# lps_regulator_rev_12.net
KiCad netlist of a schematic drawn in Altium Designer
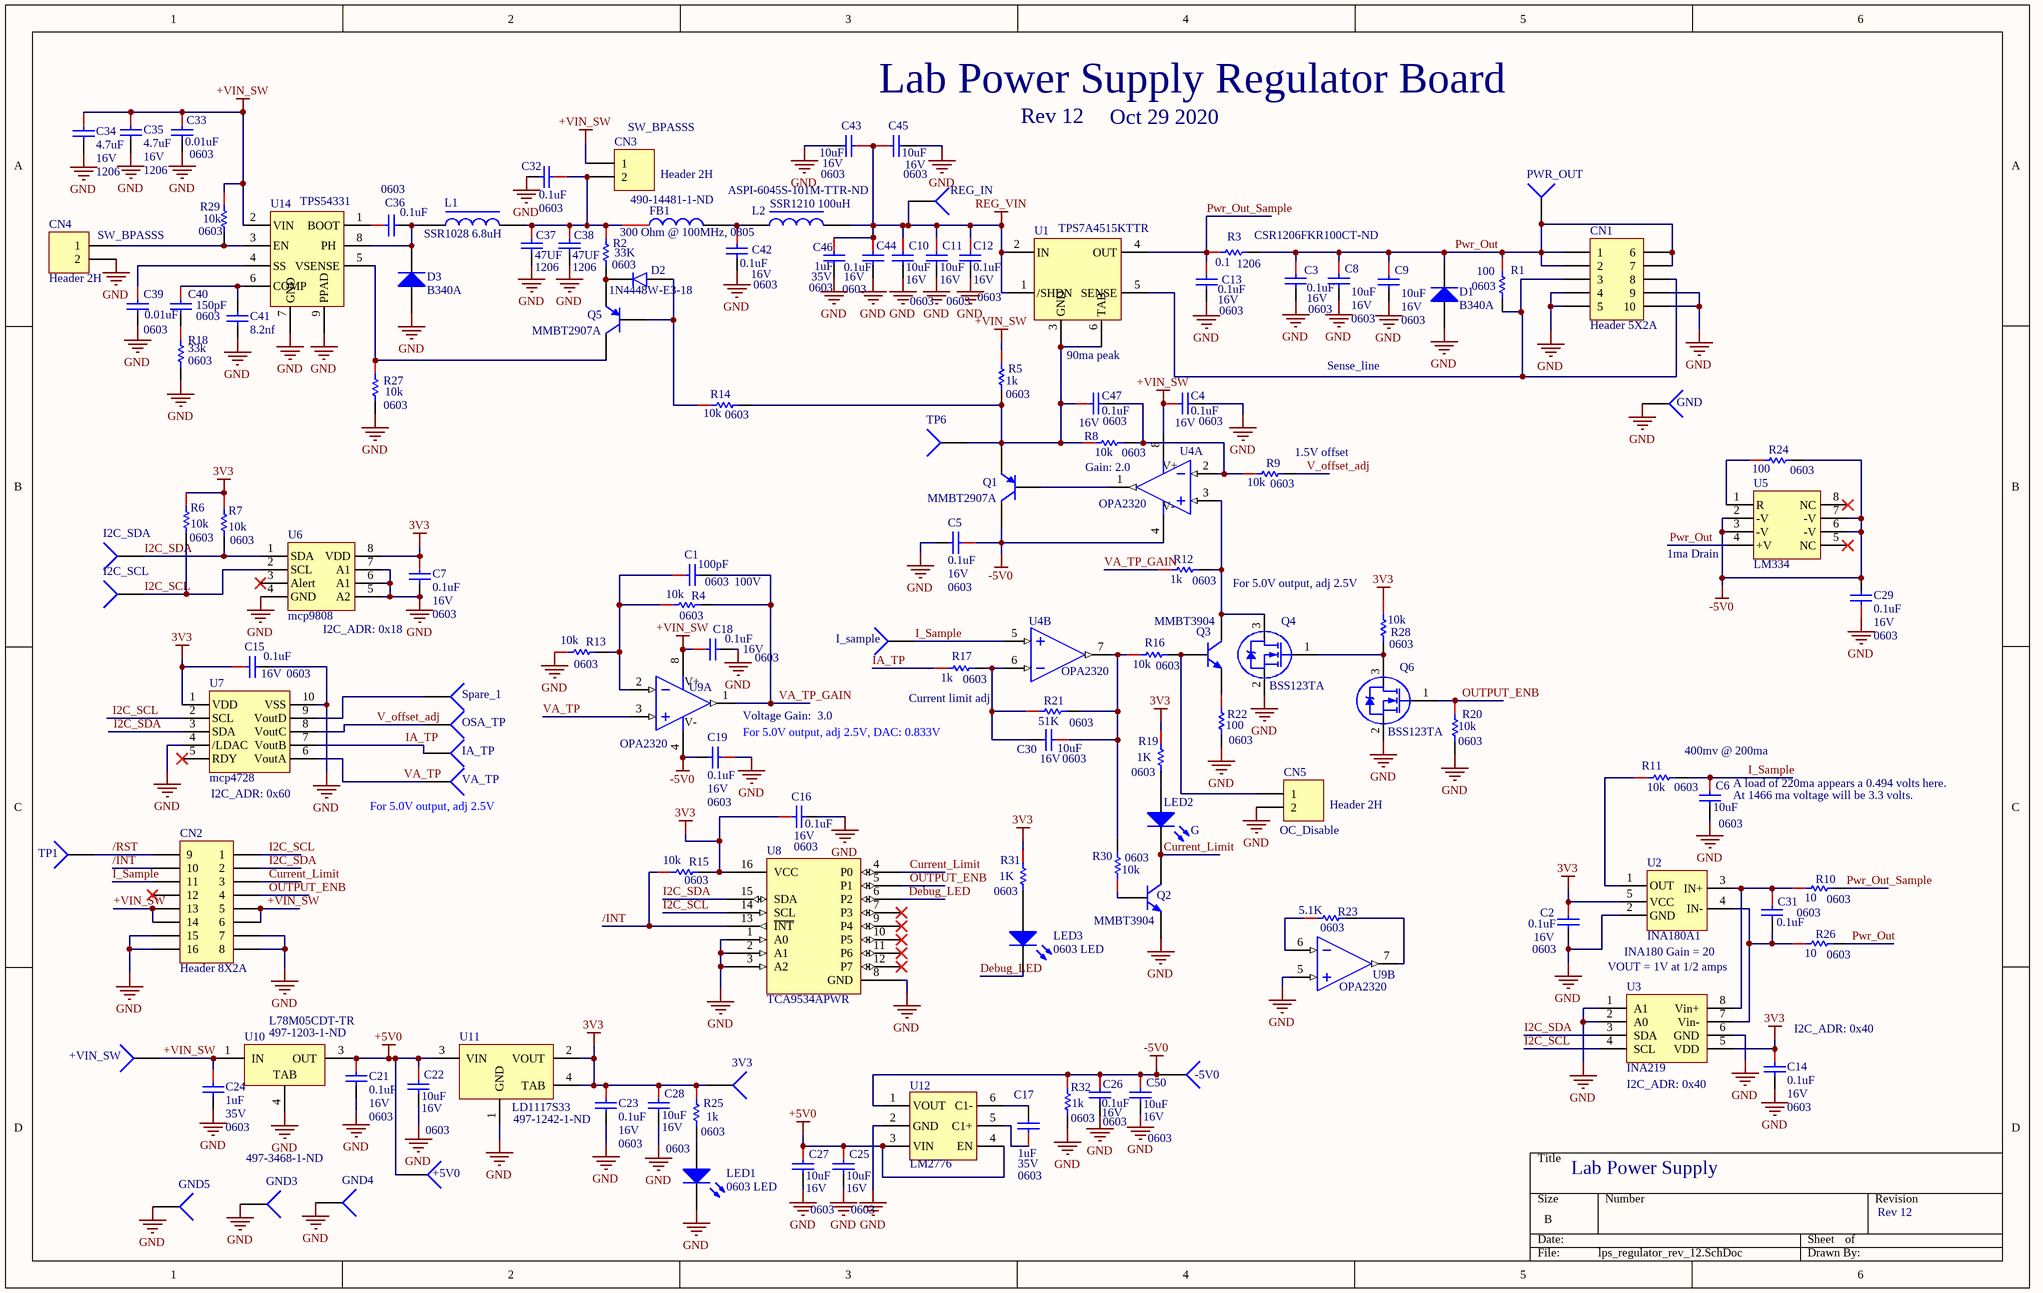
[diagram p0: lps_regulator_rev_12.SchDoc]

(export (version "E")
  (design (tool "Eeschema 10.0.6"))
  (components
    (comp (ref "+5V0")
      (value "TestPoint_BLK")
      (footprint "TestPoint-TH 42 mil")
      (description "Test Point - Black")
      (fields
        (field (name "MANUFACTURER PART NUMBER") "5001")
        (field (name "MANUFACTURER") "Keystone Electronics")
      )
      (libsource (lib "OLogic Nexus Vault") (part "TestPoint_BLK"))
    )
    (comp (ref "+VIN_SW")
      (value "TestPoint_BLK")
      (footprint "TestPoint-TH 42 mil")
      (description "Test Point - Black")
      (fields
        (field (name "MANUFACTURER PART NUMBER") "5001")
        (field (name "MANUFACTURER") "Keystone Electronics")
      )
      (libsource (lib "OLogic Nexus Vault") (part "TestPoint_BLK"))
    )
    (comp (ref "-5V0")
      (value "TestPoint_BLK")
      (footprint "TestPoint-TH 42 mil")
      (description "Test Point - Black")
      (fields
        (field (name "MANUFACTURER PART NUMBER") "5001")
        (field (name "MANUFACTURER") "Keystone Electronics")
      )
      (libsource (lib "OLogic Nexus Vault") (part "TestPoint_BLK"))
    )
    (comp (ref "3V3")
      (value "TestPoint_BLK")
      (footprint "TestPoint-TH 42 mil")
      (description "Test Point - Black")
      (fields
        (field (name "MANUFACTURER PART NUMBER") "5001")
        (field (name "MANUFACTURER") "Keystone Electronics")
      )
      (libsource (lib "OLogic Nexus Vault") (part "TestPoint_BLK"))
    )
    (comp (ref "C1")
      (value "100pF")
      (footprint "CAPC0603(1608)_N")
      (description "CAP CER 100PF 50V 5% NP0 0603")
      (fields
        (field (name "VOLTAGE (RATED)") "100V")
        (field (name "PACKAGE (IMPERIAL)") "0603")
        (field (name "TOLERANCE") "5%")
      )
      (libsource (lib "OLogic Nexus Vault") (part "=Capacitance"))
    )
    (comp (ref "C2")
      (value "0.1uF")
      (footprint "CAPC0603(1608)_M")
      (description "CAP CER 0.1UF 16V 10% X7R 0603")
      (fields
        (field (name "VOLTAGE (RATED)") "16V")
        (field (name "PACKAGE (IMPERIAL)") "0603")
        (field (name "TOLERANCE") "10%")
      )
      (libsource (lib "OLogic Nexus Vault") (part "=Capacitance"))
    )
    (comp (ref "C3")
      (value "0.1uF")
      (footprint "CAPC0603(1608)_N")
      (description "CAP CER 0.1UF 16V 10% X7R 0603")
      (fields
        (field (name "VOLTAGE (RATED)") "16V")
        (field (name "PACKAGE (IMPERIAL)") "0603")
        (field (name "TOLERANCE") "10%")
      )
      (libsource (lib "OLogic Nexus Vault") (part "=Capacitance"))
    )
    (comp (ref "C4")
      (value "0.1uF")
      (footprint "CAPC0603(1608)_N")
      (description "CAP CER 0.1UF 16V 10% X7R 0603")
      (fields
        (field (name "VOLTAGE (RATED)") "16V")
        (field (name "PACKAGE (IMPERIAL)") "0603")
        (field (name "TOLERANCE") "10%")
      )
      (libsource (lib "OLogic Nexus Vault") (part "=Capacitance"))
    )
    (comp (ref "C5")
      (value "0.1uF")
      (footprint "CAPC0603(1608)_N")
      (description "CAP CER 0.1UF 16V 10% X7R 0603")
      (fields
        (field (name "VOLTAGE (RATED)") "16V")
        (field (name "PACKAGE (IMPERIAL)") "0603")
        (field (name "TOLERANCE") "10%")
      )
      (libsource (lib "OLogic Nexus Vault") (part "=Capacitance"))
    )
    (comp (ref "C6")
      (value "10uF")
      (footprint "CAPC0603(1608)_N")
      (description "CAP CER 10UF 16V X5R 0603")
      (fields (field (name "PACKAGE (IMPERIAL)") "0603") (field (name "TOLERANCE") "10%"))
      (libsource (lib "OLogic Nexus Vault") (part "=Capacitance"))
    )
    (comp (ref "C7")
      (value "0.1uF")
      (footprint "CAPC0603(1608)_N")
      (description "CAP CER 0.1UF 16V 10% X7R 0603")
      (fields
        (field (name "VOLTAGE (RATED)") "16V")
        (field (name "PACKAGE (IMPERIAL)") "0603")
        (field (name "TOLERANCE") "10%")
      )
      (libsource (lib "OLogic Nexus Vault") (part "=Capacitance"))
    )
    (comp (ref "C8")
      (value "10uF")
      (footprint "CAPC0603(1608)_N")
      (description "CAP CER 10UF 16V X5R 0603")
      (fields
        (field (name "VOLTAGE (RATED)") "16V")
        (field (name "PACKAGE (IMPERIAL)") "0603")
        (field (name "TOLERANCE") "10%")
      )
      (libsource (lib "OLogic Nexus Vault") (part "=Capacitance"))
    )
    (comp (ref "C9")
      (value "10uF")
      (footprint "CAPC0603(1608)_N")
      (description "CAP CER 10UF 16V X5R 0603")
      (fields
        (field (name "VOLTAGE (RATED)") "16V")
        (field (name "PACKAGE (IMPERIAL)") "0603")
        (field (name "TOLERANCE") "10%")
      )
      (libsource (lib "OLogic Nexus Vault") (part "=Capacitance"))
    )
    (comp (ref "C10")
      (value "10uF")
      (footprint "CAPC0603(1608)_N")
      (description "CAP CER 10UF 16V X5R 0603")
      (fields
        (field (name "VOLTAGE (RATED)") "16V")
        (field (name "PACKAGE (IMPERIAL)") "0603")
        (field (name "TOLERANCE") "10%")
      )
      (libsource (lib "OLogic Nexus Vault") (part "=Capacitance"))
    )
    (comp (ref "C11")
      (value "10uF")
      (footprint "CAPC0603(1608)_N")
      (description "CAP CER 10UF 16V X5R 0603")
      (fields
        (field (name "VOLTAGE (RATED)") "16V")
        (field (name "PACKAGE (IMPERIAL)") "0603")
        (field (name "TOLERANCE") "10%")
      )
      (libsource (lib "OLogic Nexus Vault") (part "=Capacitance"))
    )
    (comp (ref "C12")
      (value "0.1uF")
      (footprint "CAPC0603(1608)_N")
      (description "CAP CER 0.1UF 16V 10% X7R 0603")
      (fields
        (field (name "VOLTAGE (RATED)") "16V")
        (field (name "PACKAGE (IMPERIAL)") "0603")
        (field (name "TOLERANCE") "10%")
      )
      (libsource (lib "OLogic Nexus Vault") (part "=Capacitance"))
    )
    (comp (ref "C13")
      (value "0.1uF")
      (footprint "CAPC0603(1608)_N")
      (description "CAP CER 0.1UF 16V 10% X7R 0603")
      (fields
        (field (name "VOLTAGE (RATED)") "16V")
        (field (name "PACKAGE (IMPERIAL)") "0603")
        (field (name "TOLERANCE") "10%")
      )
      (libsource (lib "OLogic Nexus Vault") (part "=Capacitance"))
    )
    (comp (ref "C14")
      (value "0.1uF")
      (footprint "CAPC0603(1608)_N")
      (description "CAP CER 0.1UF 16V 10% X7R 0603")
      (fields
        (field (name "VOLTAGE (RATED)") "16V")
        (field (name "PACKAGE (IMPERIAL)") "0603")
        (field (name "TOLERANCE") "10%")
      )
      (libsource (lib "OLogic Nexus Vault") (part "=Capacitance"))
    )
    (comp (ref "C15")
      (value "0.1uF")
      (footprint "CAPC0603(1608)_N")
      (description "CAP CER 0.1UF 16V 10% X7R 0603")
      (fields
        (field (name "VOLTAGE (RATED)") "16V")
        (field (name "PACKAGE (IMPERIAL)") "0603")
        (field (name "TOLERANCE") "10%")
      )
      (libsource (lib "OLogic Nexus Vault") (part "=Capacitance"))
    )
    (comp (ref "C16")
      (value "0.1uF")
      (footprint "CAPC0603(1608)_N")
      (description "CAP CER 0.1UF 16V 10% X7R 0603")
      (fields
        (field (name "VOLTAGE (RATED)") "16V")
        (field (name "PACKAGE (IMPERIAL)") "0603")
        (field (name "TOLERANCE") "10%")
      )
      (libsource (lib "OLogic Nexus Vault") (part "=Capacitance"))
    )
    (comp (ref "C17")
      (value "1uF")
      (footprint "CAPC0603(1608)_N")
      (description "CAP CER 1UF 35V 10% X5R 0603")
      (fields
        (field (name "VOLTAGE (RATED)") "35V")
        (field (name "PACKAGE (IMPERIAL)") "0603")
        (field (name "TOLERANCE") "10%")
      )
      (libsource (lib "OLogic Nexus Vault") (part "=Capacitance"))
    )
    (comp (ref "C18")
      (value "0.1uF")
      (footprint "CAPC0603(1608)_N")
      (description "CAP CER 0.1UF 16V 10% X7R 0603")
      (fields
        (field (name "VOLTAGE (RATED)") "16V")
        (field (name "PACKAGE (IMPERIAL)") "0603")
        (field (name "TOLERANCE") "10%")
      )
      (libsource (lib "OLogic Nexus Vault") (part "=Capacitance"))
    )
    (comp (ref "C19")
      (value "0.1uF")
      (footprint "CAPC0603(1608)_N")
      (description "CAP CER 0.1UF 16V 10% X7R 0603")
      (fields
        (field (name "VOLTAGE (RATED)") "16V")
        (field (name "PACKAGE (IMPERIAL)") "0603")
        (field (name "TOLERANCE") "10%")
      )
      (libsource (lib "OLogic Nexus Vault") (part "=Capacitance"))
    )
    (comp (ref "C21")
      (value "0.1uF")
      (footprint "CAPC0603(1608)_N")
      (description "CAP CER 0.1UF 16V 10% X7R 0603")
      (fields
        (field (name "VOLTAGE (RATED)") "16V")
        (field (name "PACKAGE (IMPERIAL)") "0603")
        (field (name "TOLERANCE") "10%")
      )
      (libsource (lib "OLogic Nexus Vault") (part "=Capacitance"))
    )
    (comp (ref "C22")
      (value "10uF")
      (footprint "CAPC0603(1608)_N")
      (description "CAP CER 10UF 16V X5R 0603")
      (fields
        (field (name "VOLTAGE (RATED)") "16V")
        (field (name "PACKAGE (IMPERIAL)") "0603")
        (field (name "TOLERANCE") "10%")
      )
      (libsource (lib "OLogic Nexus Vault") (part "=Capacitance"))
    )
    (comp (ref "C23")
      (value "0.1uF")
      (footprint "CAPC0603(1608)_N")
      (description "CAP CER 0.1UF 16V 10% X7R 0603")
      (fields
        (field (name "VOLTAGE (RATED)") "16V")
        (field (name "PACKAGE (IMPERIAL)") "0603")
        (field (name "TOLERANCE") "10%")
      )
      (libsource (lib "OLogic Nexus Vault") (part "=Capacitance"))
    )
    (comp (ref "C24")
      (value "1uF")
      (footprint "CAPC0603(1608)_N")
      (description "CAP CER 1UF 35V 10% X5R 0603")
      (fields
        (field (name "VOLTAGE (RATED)") "35V")
        (field (name "PACKAGE (IMPERIAL)") "0603")
        (field (name "TOLERANCE") "10%")
      )
      (libsource (lib "OLogic Nexus Vault") (part "=Capacitance"))
    )
    (comp (ref "C25")
      (value "10uF")
      (footprint "CAPC0603(1608)_N")
      (description "CAP CER 10UF 16V X5R 0603")
      (fields
        (field (name "VOLTAGE (RATED)") "16V")
        (field (name "PACKAGE (IMPERIAL)") "0603")
        (field (name "TOLERANCE") "10%")
      )
      (libsource (lib "OLogic Nexus Vault") (part "=Capacitance"))
    )
    (comp (ref "C26")
      (value "0.1uF")
      (footprint "CAPC0603(1608)_N")
      (description "CAP CER 0.1UF 16V 10% X7R 0603")
      (fields
        (field (name "VOLTAGE (RATED)") "16V")
        (field (name "PACKAGE (IMPERIAL)") "0603")
        (field (name "TOLERANCE") "10%")
      )
      (libsource (lib "OLogic Nexus Vault") (part "=Capacitance"))
    )
    (comp (ref "C27")
      (value "10uF")
      (footprint "CAPC0603(1608)_N")
      (description "CAP CER 10UF 16V X5R 0603")
      (fields
        (field (name "VOLTAGE (RATED)") "16V")
        (field (name "PACKAGE (IMPERIAL)") "0603")
        (field (name "TOLERANCE") "10%")
      )
      (libsource (lib "OLogic Nexus Vault") (part "=Capacitance"))
    )
    (comp (ref "C28")
      (value "10uF")
      (footprint "CAPC0603(1608)_N")
      (description "CAP CER 10UF 16V X5R 0603")
      (fields
        (field (name "VOLTAGE (RATED)") "16V")
        (field (name "PACKAGE (IMPERIAL)") "0603")
        (field (name "TOLERANCE") "10%")
      )
      (libsource (lib "OLogic Nexus Vault") (part "=Capacitance"))
    )
    (comp (ref "C29")
      (value "0.1uF")
      (footprint "CAPC0603(1608)_N")
      (description "CAP CER 0.1UF 16V 10% X7R 0603")
      (fields
        (field (name "VOLTAGE (RATED)") "16V")
        (field (name "PACKAGE (IMPERIAL)") "0603")
        (field (name "TOLERANCE") "10%")
      )
      (libsource (lib "OLogic Nexus Vault") (part "=Capacitance"))
    )
    (comp (ref "C30")
      (value "10uF")
      (footprint "CAPC0603(1608)_N")
      (description "CAP CER 0.1UF 16V 10% X7R 0603")
      (fields
        (field (name "VOLTAGE (RATED)") "16V")
        (field (name "PACKAGE (IMPERIAL)") "0603")
        (field (name "TOLERANCE") "10%")
      )
      (libsource (lib "OLogic Nexus Vault") (part "=Capacitance"))
    )
    (comp (ref "C31")
      (value "0.1uF")
      (footprint "CAPC0603(1608)_N")
      (description "CAP CER 0.1UF 16V 10% X7R 0603")
      (fields (field (name "PACKAGE (IMPERIAL)") "0603") (field (name "TOLERANCE") "10%"))
      (libsource (lib "OLogic Nexus Vault") (part "=Capacitance"))
    )
    (comp (ref "C32")
      (value "0.1uF")
      (footprint "CAPC0603(1608)_N")
      (description "CAP CER 0.1UF 16V 10% X7R 0603")
      (fields (field (name "PACKAGE (IMPERIAL)") "0603") (field (name "TOLERANCE") "10%"))
      (libsource (lib "OLogic Nexus Vault") (part "=Capacitance"))
    )
    (comp (ref "C33")
      (value "0.01uF")
      (footprint "CAPC0603(1608)_N")
      (description "CAP CER 0.01uF 50V 10% X7R 0603")
      (fields (field (name "PACKAGE (IMPERIAL)") "0603") (field (name "TOLERANCE") "10%"))
      (libsource (lib "OLogic Nexus Vault") (part "=Capacitance"))
    )
    (comp (ref "C34")
      (value "4.7uF")
      (footprint "CAPC1206(3216)_N")
      (description "CAP CER 4.7UF 50V 10% X7R 1206")
      (fields
        (field (name "VOLTAGE (RATED)") "16V")
        (field (name "PACKAGE (IMPERIAL)") "1206")
        (field (name "TOLERANCE") "10%")
      )
      (libsource (lib "OLogic Nexus Vault") (part "=Capacitance"))
    )
    (comp (ref "C35")
      (value "4.7uF")
      (footprint "CAPC1206(3216)_N")
      (description "CAP CER 4.7UF 50V 10% X7R 1206")
      (fields
        (field (name "VOLTAGE (RATED)") "16V")
        (field (name "PACKAGE (IMPERIAL)") "1206")
        (field (name "TOLERANCE") "10%")
      )
      (libsource (lib "OLogic Nexus Vault") (part "=Capacitance"))
    )
    (comp (ref "C36")
      (value "0.1uF")
      (footprint "CAPC0603(1608)_N")
      (description "CAP CER 0.1UF 16V 10% X7R 0603")
      (fields (field (name "PACKAGE (IMPERIAL)") "0603") (field (name "TOLERANCE") "10%"))
      (libsource (lib "OLogic Nexus Vault") (part "=Capacitance"))
    )
    (comp (ref "C37")
      (value "47UF")
      (footprint "CAPC1206(3216)_N")
      (description "CAP CER 47UF 25V 1206")
      (fields (field (name "PACKAGE (IMPERIAL)") "1206") (field (name "TOLERANCE") "20%"))
      (libsource (lib "OLogic Nexus Vault") (part "=Capacitance"))
    )
    (comp (ref "C38")
      (value "47UF")
      (footprint "CAPC1206(3216)_N")
      (description "CAP CER 47UF 25V 1206")
      (fields (field (name "PACKAGE (IMPERIAL)") "1206") (field (name "TOLERANCE") "20%"))
      (libsource (lib "OLogic Nexus Vault") (part "=Capacitance"))
    )
    (comp (ref "C39")
      (value "0.01uF")
      (footprint "CAPC0603(1608)_N")
      (description "CAP CER 22PF 50V 5% NP0 0603")
      (fields (field (name "PACKAGE (IMPERIAL)") "0603") (field (name "TOLERANCE") "5%"))
      (libsource (lib "OLogic Nexus Vault") (part "=Capacitance"))
    )
    (comp (ref "C40")
      (value "150pF")
      (footprint "CAPC0603(1608)_N")
      (description "CAP CER 1UF 35V 10% X5R 0603")
      (fields (field (name "PACKAGE (IMPERIAL)") "0603") (field (name "TOLERANCE") "10%"))
      (libsource (lib "OLogic Nexus Vault") (part "=Capacitance"))
    )
    (comp (ref "C41")
      (value "8.2nf")
      (footprint "CAPC1608X87X35ML15T15")
      (description "CAP CER 820PF 50V X7R 0603")
      (fields (field (name "VOLTAGE") "50V") (field (name "TOLERANCE") "10%"))
      (libsource (lib "OLogic Nexus Vault") (part "CAP"))
    )
    (comp (ref "C42")
      (value "0.1uF")
      (footprint "CAPC0603(1608)_N")
      (description "CAP CER 0.1UF 16V 10% X7R 0603")
      (fields
        (field (name "VOLTAGE (RATED)") "16V")
        (field (name "PACKAGE (IMPERIAL)") "0603")
        (field (name "TOLERANCE") "10%")
      )
      (libsource (lib "OLogic Nexus Vault") (part "=Capacitance"))
    )
    (comp (ref "C43")
      (value "10uF")
      (footprint "CAPC0603(1608)_N")
      (description "CAP CER 10UF 16V X5R 0603")
      (fields
        (field (name "VOLTAGE (RATED)") "16V")
        (field (name "PACKAGE (IMPERIAL)") "0603")
        (field (name "TOLERANCE") "10%")
      )
      (libsource (lib "OLogic Nexus Vault") (part "=Capacitance"))
    )
    (comp (ref "C44")
      (value "0.1uF")
      (footprint "CAPC0603(1608)_N")
      (description "CAP CER 0.1UF 16V 10% X7R 0603")
      (fields
        (field (name "VOLTAGE (RATED)") "16V")
        (field (name "PACKAGE (IMPERIAL)") "0603")
        (field (name "TOLERANCE") "10%")
      )
      (libsource (lib "OLogic Nexus Vault") (part "=Capacitance"))
    )
    (comp (ref "C45")
      (value "10uF")
      (footprint "CAPC0603(1608)_N")
      (description "CAP CER 10UF 16V X5R 0603")
      (fields
        (field (name "VOLTAGE (RATED)") "16V")
        (field (name "PACKAGE (IMPERIAL)") "0603")
        (field (name "TOLERANCE") "10%")
      )
      (libsource (lib "OLogic Nexus Vault") (part "=Capacitance"))
    )
    (comp (ref "C46")
      (value "1uF")
      (footprint "CAPC0603(1608)_N")
      (description "CAP CER 1UF 35V 10% X5R 0603")
      (fields
        (field (name "VOLTAGE (RATED)") "35V")
        (field (name "PACKAGE (IMPERIAL)") "0603")
        (field (name "TOLERANCE") "10%")
      )
      (libsource (lib "OLogic Nexus Vault") (part "=Capacitance"))
    )
    (comp (ref "C47")
      (value "0.1uF")
      (footprint "CAPC0603(1608)_N")
      (description "CAP CER 0.1UF 16V 10% X7R 0603")
      (fields
        (field (name "VOLTAGE (RATED)") "16V")
        (field (name "PACKAGE (IMPERIAL)") "0603")
        (field (name "TOLERANCE") "10%")
      )
      (libsource (lib "OLogic Nexus Vault") (part "=Capacitance"))
    )
    (comp (ref "C50")
      (value "10uF")
      (footprint "CAPC0603(1608)_N")
      (description "CAP CER 10UF 16V X5R 0603")
      (fields
        (field (name "VOLTAGE (RATED)") "16V")
        (field (name "PACKAGE (IMPERIAL)") "0603")
        (field (name "TOLERANCE") "10%")
      )
      (libsource (lib "OLogic Nexus Vault") (part "=Capacitance"))
    )
    (comp (ref "CN1")
      (value "Header 5X2A")
      (footprint "HDR2X5_CEN")
      (description "Header, 5-Pin, Dual row")
      (fields (field (name "PUBLISHER") "Altium Limited"))
      (libsource (lib "OLogic Nexus Vault") (part "Header 5X2A"))
    )
    (comp (ref "CN2")
      (value "Header 8X2A")
      (footprint "HDR2X8_CEN")
      (description "Header, 8-Pin, Dual row")
      (fields (field (name "PUBLISHER") "Altium Limited"))
      (libsource (lib "OLogic Nexus Vault") (part "Header 8X2A"))
    )
    (comp (ref "CN3")
      (value "Header 2H")
      (footprint "HDR1X2H")
      (description "Header, 2-Pin, Right Angle")
      (fields
        (field (name "MANUFACTURER PART NUMBER") "M20-9960245")
        (field (name "MANUFACTURER") "Harwin Inc.")
        (field (name "PUBLISHER") "Altium Limited")
      )
      (libsource (lib "OLogic Nexus Vault") (part "Header 2H"))
    )
    (comp (ref "CN4")
      (value "Header 2H")
      (footprint "HDR1X2H")
      (description "Header, 2-Pin, Right Angle")
      (fields
        (field (name "MANUFACTURER PART NUMBER") "M20-9960245")
        (field (name "MANUFACTURER") "Harwin Inc.")
        (field (name "PUBLISHER") "Altium Limited")
      )
      (libsource (lib "") (part "Header 2H_1"))
    )
    (comp (ref "CN5")
      (value "Header 2H")
      (footprint "HDR1X2H")
      (description "Header, 2-Pin, Right Angle")
      (fields
        (field (name "MANUFACTURER PART NUMBER") "M20-9960245")
        (field (name "MANUFACTURER") "Harwin Inc.")
        (field (name "PUBLISHER") "Altium Limited")
      )
      (libsource (lib "OLogic Nexus Vault") (part "Header 2H"))
    )
    (comp (ref "D1")
      (value "B340A")
      (footprint "DO-214AC")
      (description "DIODE SCHOTTKY 60V 3A")
      (fields
        (field (name "MANUFACTURER") "Micro Commercial Co")
        (field (name "MANUFACTURER PART NUMBER") "SK36A-LTP")
      )
      (libsource (lib "OLogic Nexus Vault") (part "SK36A-LTP"))
    )
    (comp (ref "D2")
      (value "1N4448W-E3-18")
      (footprint "SOD123")
      (description "Diodes - General Purpose, Power, Switching 100 Volt 500mA 4ns")
      (libsource (lib "OLogic Nexus Vault") (part "1N4448W-E3-18"))
    )
    (comp (ref "D3")
      (value "B340A")
      (footprint "DO-214AC")
      (description "DIODE SCHOTTKY 60V 3A")
      (fields
        (field (name "MANUFACTURER") "Micro Commercial Co")
        (field (name "MANUFACTURER PART NUMBER") "SK36A-LTP")
      )
      (libsource (lib "OLogic Nexus Vault") (part "SK36A-LTP"))
    )
    (comp (ref "FB1")
      (value "300 Ohm @ 100MHz, 0805")
      (footprint "RESC0805(2012)_N")
      (description "600 Ohms @ 100MHz 1 Signal Line Ferrite Bead 0805 (2012 Metric) 2A 150mOhm")
      (fields
        (field (name "MANUFACTURER PART NUMBER") "742792040")
        (field (name "MANUFACTURER") "Wurth Electronics Inc")
        (field (name "CREATOR") "osman")
      )
      (libsource (lib "OLogic Nexus Vault") (part "OL_Ferrite"))
    )
    (comp (ref "GND")
      (value "TestPoint_BLK")
      (footprint "TestPoint-TH 42 mil")
      (description "Test Point - Black")
      (fields
        (field (name "MANUFACTURER PART NUMBER") "5001")
        (field (name "MANUFACTURER") "Keystone Electronics")
      )
      (libsource (lib "OLogic Nexus Vault") (part "TestPoint_BLK"))
    )
    (comp (ref "GND3")
      (value "TestPoint_BLK")
      (footprint "TestPoint-TH 42 mil")
      (description "Test Point - Black")
      (fields
        (field (name "MANUFACTURER PART NUMBER") "5001")
        (field (name "MANUFACTURER") "Keystone Electronics")
      )
      (libsource (lib "OLogic Nexus Vault") (part "TestPoint_BLK"))
    )
    (comp (ref "GND4")
      (value "TestPoint_BLK")
      (footprint "TestPoint-TH 42 mil")
      (description "Test Point - Black")
      (fields
        (field (name "MANUFACTURER PART NUMBER") "5001")
        (field (name "MANUFACTURER") "Keystone Electronics")
      )
      (libsource (lib "OLogic Nexus Vault") (part "TestPoint_BLK"))
    )
    (comp (ref "GND5")
      (value "TestPoint_BLK")
      (footprint "TestPoint-TH 42 mil")
      (description "Test Point - Black")
      (fields
        (field (name "MANUFACTURER PART NUMBER") "5001")
        (field (name "MANUFACTURER") "Keystone Electronics")
      )
      (libsource (lib "OLogic Nexus Vault") (part "TestPoint_BLK"))
    )
    (comp (ref "I2C_SCL")
      (value "TestPoint_BLK")
      (footprint "TestPoint-TH 42 mil")
      (description "Test Point - Black")
      (fields
        (field (name "MANUFACTURER PART NUMBER") "5001")
        (field (name "MANUFACTURER") "Keystone Electronics")
      )
      (libsource (lib "OLogic Nexus Vault") (part "TestPoint_BLK"))
    )
    (comp (ref "I2C_SDA")
      (value "TestPoint_BLK")
      (footprint "TestPoint-TH 42 mil")
      (description "Test Point - Black")
      (fields
        (field (name "MANUFACTURER PART NUMBER") "5001")
        (field (name "MANUFACTURER") "Keystone Electronics")
      )
      (libsource (lib "OLogic Nexus Vault") (part "TestPoint_BLK"))
    )
    (comp (ref "IA_TP")
      (value "TestPoint_BLK")
      (footprint "TestPoint-TH 42 mil")
      (description "Test Point - Black")
      (fields
        (field (name "MANUFACTURER PART NUMBER") "5001")
        (field (name "MANUFACTURER") "Keystone Electronics")
      )
      (libsource (lib "OLogic Nexus Vault") (part "TestPoint_BLK"))
    )
    (comp (ref "I_sample")
      (value "TestPoint_BLK")
      (footprint "TestPoint-TH 42 mil")
      (description "Test Point - Black")
      (fields
        (field (name "MANUFACTURER PART NUMBER") "5001")
        (field (name "MANUFACTURER") "Keystone Electronics")
      )
      (libsource (lib "OLogic Nexus Vault") (part "TestPoint_BLK"))
    )
    (comp (ref "L1")
      (value "SSR1028 6.8uH")
      (footprint "SRU1028")
      (description "INDUCTOR 6.8uH  SMD")
      (fields (field (name "TOLERANCE") "30%"))
      (libsource (lib "OLogic Nexus Vault") (part "SSR1028"))
    )
    (comp (ref "L2")
      (value "SSR1210 100uH")
      (footprint "SRR1210")
      (description "INDUCTOR 100uH 2.2A SMD")
      (fields (field (name "TOLERANCE") "30%"))
      (libsource (lib "OLogic Nexus Vault") (part "SSR1210"))
    )
    (comp (ref "LED1")
      (value "0603 LED")
      (footprint "SM-LED-0603")
      (description "0603 SMD LED")
      (libsource (lib "OLogic Nexus Vault") (part "LED_SINGLE_GENERIC"))
    )
    (comp (ref "LED2")
      (value "G")
      (footprint "SM-LED-0603")
      (description "0603 SMD LED")
      (libsource (lib "OLogic-Diode-Opto-LED") (part "0603 LED"))
    )
    (comp (ref "LED3")
      (value "0603 LED")
      (footprint "SM-LED-0603")
      (description "0603 SMD LED")
      (libsource (lib "OLogic Nexus Vault") (part "LED_SINGLE_GENERIC"))
    )
    (comp (ref "OSA_TP")
      (value "TestPoint_BLK")
      (footprint "TestPoint-TH 42 mil")
      (description "Test Point - Black")
      (fields
        (field (name "MANUFACTURER PART NUMBER") "5001")
        (field (name "MANUFACTURER") "Keystone Electronics")
      )
      (libsource (lib "OLogic Nexus Vault") (part "TestPoint_BLK"))
    )
    (comp (ref "PWR_OUT")
      (value "TestPoint_BLK")
      (footprint "TestPoint-TH 42 mil")
      (description "Test Point - Black")
      (fields
        (field (name "MANUFACTURER PART NUMBER") "5001")
        (field (name "MANUFACTURER") "Keystone Electronics")
      )
      (libsource (lib "OLogic Nexus Vault") (part "TestPoint_BLK"))
    )
    (comp (ref "Q1")
      (value "MMBT2907A")
      (footprint "SOT23")
      (description "PNP General Purpose Amplifier")
      (fields (field (name "MANUFACTURER") "Fairchild Semiconductor"))
      (libsource (lib "OLogic Nexus Vault") (part "MMBT2907A"))
    )
    (comp (ref "Q2")
      (value "MMBT3904")
      (footprint "SOT23")
      (description "NPN General Purpose Amplifier")
      (fields (field (name "MANUFACTURER") "ON Semiconductor") (field (name "MPN") "MMBT3904WT1G"))
      (libsource (lib "OLogic-Trans-Drivers") (part "MMBT3904"))
    )
    (comp (ref "Q3")
      (value "MMBT3904")
      (footprint "SOT23")
      (description "NPN General Purpose Amplifier")
      (fields (field (name "MANUFACTURER") "ON Semiconductor") (field (name "MPN") "MMBT3904WT1G"))
      (libsource (lib "OLogic-Trans-Drivers") (part "MMBT3904"))
    )
    (comp (ref "Q4")
      (value "BSS123TA")
      (footprint "SOT23-3L")
      (description "MOSFET N-CH 100V 170MA SOT23-3")
      (fields (field (name "MANUFACTURER") "Diodes Incorporated"))
      (libsource (lib "OLogic Nexus Vault") (part "BSS123TA"))
    )
    (comp (ref "Q5")
      (value "MMBT2907A")
      (footprint "SOT23")
      (description "PNP General Purpose Amplifier")
      (fields (field (name "MANUFACTURER") "Fairchild Semiconductor"))
      (libsource (lib "OLogic Nexus Vault") (part "MMBT2907A"))
    )
    (comp (ref "Q6")
      (value "BSS123TA")
      (footprint "SOT23-3L")
      (description "MOSFET N-CH 100V 170MA SOT23-3")
      (fields (field (name "MANUFACTURER") "Diodes Incorporated"))
      (libsource (lib "OLogic Nexus Vault") (part "BSS123TA"))
    )
    (comp (ref "R1")
      (value "100")
      (footprint "RESC0603(1608)_N")
      (description "RES 100 OHM 1% 1/10W 0603 2017")
      (fields
        (field (name "PACKAGE (IMPERIAL)") "0603")
        (field (name "POWER") "100mW")
        (field (name "TOLERANCE") "1%")
        (field (name "RESISTANCE") "100")
      )
      (libsource (lib "OLogic Nexus Vault") (part "=Resistance"))
    )
    (comp (ref "R2")
      (value "10K")
      (footprint "RESC0603(1608)_N")
      (description "RES 10K OHM 1/10W 1% 0603 SMD")
      (fields
        (field (name "PACKAGE (IMPERIAL)") "0603")
        (field (name "RESISTANCE") "33K")
        (field (name "POWER") "100mW")
        (field (name "TOLERANCE") "1%")
      )
      (libsource (lib "OLogic Nexus Vault") (part "=Resistance"))
    )
    (comp (ref "R3")
      (value "0.33")
      (footprint "RESC1206(3216)_N")
      (description "RES 0.33 OHM 1% 1/4W 1206")
      (fields
        (field (name "PACKAGE (IMPERIAL)") "1206")
        (field (name "RESISTANCE") "0.1")
        (field (name "POWER") "250mW")
        (field (name "TOLERANCE") "1%")
      )
      (libsource (lib "OLogic Nexus Vault") (part "=Resistance"))
    )
    (comp (ref "R4")
      (value "10k")
      (footprint "RESC0603(1608)_M")
      (description "RES 10K OHM 0.1% 1/10W 0603")
      (fields
        (field (name "PACKAGE (IMPERIAL)") "0603")
        (field (name "RESISTANCE") "10k")
        (field (name "TOLERANCE") "0.1%")
        (field (name "POWER") "100mW")
      )
      (libsource (lib "OLogic Nexus Vault") (part "=Resistance"))
    )
    (comp (ref "R5")
      (value "10K")
      (footprint "RESC0603(1608)_N")
      (description "RES 10K OHM 1/10W 1% 0603 SMD")
      (fields
        (field (name "PACKAGE (IMPERIAL)") "0603")
        (field (name "RESISTANCE") "1k")
        (field (name "POWER") "100mW")
        (field (name "TOLERANCE") "1%")
      )
      (libsource (lib "OLogic Nexus Vault") (part "=Resistance"))
    )
    (comp (ref "R6")
      (value "10K")
      (footprint "RESC0603(1608)_N")
      (description "RES 10K OHM 1/10W 1% 0603 SMD")
      (fields
        (field (name "PACKAGE (IMPERIAL)") "0603")
        (field (name "RESISTANCE") "10k")
        (field (name "POWER") "100mW")
        (field (name "TOLERANCE") "1%")
      )
      (libsource (lib "OLogic Nexus Vault") (part "=Resistance"))
    )
    (comp (ref "R7")
      (value "10K")
      (footprint "RESC0603(1608)_N")
      (description "RES 10K OHM 1/10W 1% 0603 SMD")
      (fields
        (field (name "PACKAGE (IMPERIAL)") "0603")
        (field (name "RESISTANCE") "10k")
        (field (name "POWER") "100mW")
        (field (name "TOLERANCE") "1%")
      )
      (libsource (lib "OLogic Nexus Vault") (part "=Resistance"))
    )
    (comp (ref "R8")
      (value "10K")
      (footprint "RESC0603(1608)_N")
      (description "RES 10K OHM 1/10W 1% 0603 SMD")
      (fields
        (field (name "PACKAGE (IMPERIAL)") "0603")
        (field (name "RESISTANCE") "10k")
        (field (name "POWER") "100mW")
        (field (name "TOLERANCE") "1%")
      )
      (libsource (lib "OLogic Nexus Vault") (part "=Resistance"))
    )
    (comp (ref "R9")
      (value "10K")
      (footprint "RESC0603(1608)_N")
      (description "RES 10K OHM 1/10W 1% 0603 SMD")
      (fields
        (field (name "PACKAGE (IMPERIAL)") "0603")
        (field (name "RESISTANCE") "10k")
        (field (name "POWER") "100mW")
        (field (name "TOLERANCE") "1%")
      )
      (libsource (lib "OLogic Nexus Vault") (part "=Resistance"))
    )
    (comp (ref "R10")
      (value "10K")
      (footprint "RESC0603(1608)_M")
      (description "RES 10K OHM 1/10W 1% 0603 SMD")
      (fields
        (field (name "PACKAGE (IMPERIAL)") "0603")
        (field (name "RESISTANCE") "10")
        (field (name "POWER") "100mW")
        (field (name "TOLERANCE") "1%")
      )
      (libsource (lib "OLogic Nexus Vault") (part "=Resistance"))
    )
    (comp (ref "R11")
      (value "10K")
      (footprint "RESC0603(1608)_M")
      (description "RES 10K OHM 1/10W 1% 0603 SMD")
      (fields
        (field (name "PACKAGE (IMPERIAL)") "0603")
        (field (name "RESISTANCE") "10k")
        (field (name "POWER") "100mW")
        (field (name "TOLERANCE") "1%")
      )
      (libsource (lib "OLogic Nexus Vault") (part "=Resistance"))
    )
    (comp (ref "R12")
      (value "1.0K")
      (footprint "RESC0603(1608)_N")
      (description "RES 1K OHM 1% 1/10W 0603")
      (fields
        (field (name "PACKAGE (IMPERIAL)") "0603")
        (field (name "POWER") "100mW")
        (field (name "RESISTANCE") "1k")
        (field (name "TOLERANCE") "1%")
      )
      (libsource (lib "OLogic Nexus Vault") (part "=Resistance"))
    )
    (comp (ref "R13")
      (value "10k")
      (footprint "RESC0603(1608)_M")
      (description "RES 10K OHM 0.1% 1/10W 0603")
      (fields
        (field (name "PACKAGE (IMPERIAL)") "0603")
        (field (name "RESISTANCE") "10k")
        (field (name "TOLERANCE") "0.1%")
        (field (name "POWER") "100mW")
      )
      (libsource (lib "OLogic Nexus Vault") (part "=Resistance"))
    )
    (comp (ref "R14")
      (value "10K")
      (footprint "RESC0603(1608)_N")
      (description "RES 10K OHM 1/10W 1% 0603 SMD")
      (fields
        (field (name "PACKAGE (IMPERIAL)") "0603")
        (field (name "RESISTANCE") "10k")
        (field (name "POWER") "100mW")
        (field (name "TOLERANCE") "1%")
      )
      (libsource (lib "OLogic Nexus Vault") (part "=Resistance"))
    )
    (comp (ref "R15")
      (value "10k")
      (footprint "RESC0603(1608)_M")
      (description "RES 10K OHM 0.1% 1/10W 0603")
      (fields
        (field (name "PACKAGE (IMPERIAL)") "0603")
        (field (name "RESISTANCE") "10k")
        (field (name "TOLERANCE") "0.1%")
        (field (name "POWER") "100mW")
      )
      (libsource (lib "OLogic Nexus Vault") (part "=Resistance"))
    )
    (comp (ref "R16")
      (value "1.0K")
      (footprint "RESC0603(1608)_N")
      (description "RES 1K OHM 1% 1/10W 0603")
      (fields
        (field (name "PACKAGE (IMPERIAL)") "0603")
        (field (name "POWER") "100mW")
        (field (name "RESISTANCE") "10k")
        (field (name "TOLERANCE") "1%")
      )
      (libsource (lib "OLogic Nexus Vault") (part "=Resistance"))
    )
    (comp (ref "R17")
      (value "1.0K")
      (footprint "RESC0603(1608)_N")
      (description "RES 1K OHM 1% 1/10W 0603")
      (fields
        (field (name "PACKAGE (IMPERIAL)") "0603")
        (field (name "POWER") "100mW")
        (field (name "RESISTANCE") "1k")
        (field (name "TOLERANCE") "1%")
      )
      (libsource (lib "OLogic Nexus Vault") (part "=Resistance"))
    )
    (comp (ref "R18")
      (value "33K")
      (footprint "RESC0603(1608)_N")
      (description "RES 33K OHM 1/10W 5% 0603 SMD")
      (fields
        (field (name "PACKAGE (IMPERIAL)") "0603")
        (field (name "TOLERANCE") "5%")
        (field (name "POWER") "100mW")
        (field (name "RESISTANCE") "33k")
      )
      (libsource (lib "OLogic Nexus Vault") (part "=Resistance"))
    )
    (comp (ref "R19")
      (value "1.0K")
      (footprint "RESC0603(1608)_N")
      (description "RES 1K OHM 1% 1/10W 0603")
      (fields
        (field (name "PACKAGE (IMPERIAL)") "0603")
        (field (name "POWER") "100mW")
        (field (name "RESISTANCE") "1K")
        (field (name "TOLERANCE") "1%")
      )
      (libsource (lib "OLogic Nexus Vault") (part "=Resistance"))
    )
    (comp (ref "R20")
      (value "10K")
      (footprint "RESC0603(1608)_N")
      (description "RES 10K OHM 1/10W 1% 0603 SMD")
      (fields
        (field (name "PACKAGE (IMPERIAL)") "0603")
        (field (name "RESISTANCE") "10k")
        (field (name "POWER") "100mW")
        (field (name "TOLERANCE") "1%")
      )
      (libsource (lib "OLogic Nexus Vault") (part "=Resistance"))
    )
    (comp (ref "R21")
      (value "100K")
      (footprint "RESC0603(1608)_N")
      (description "RES 100K OHM 1% 1/10W 0603")
      (fields
        (field (name "PACKAGE (IMPERIAL)") "0603")
        (field (name "RESISTANCE") "51K")
        (field (name "POWER") "100mW")
        (field (name "TOLERANCE") "1%")
      )
      (libsource (lib "OLogic Nexus Vault") (part "=Resistance"))
    )
    (comp (ref "R22")
      (value "1.0K")
      (footprint "RESC0603(1608)_N")
      (description "RES 1K OHM 1% 1/10W 0603")
      (fields
        (field (name "PACKAGE (IMPERIAL)") "0603")
        (field (name "POWER") "100mW")
        (field (name "RESISTANCE") "100")
        (field (name "TOLERANCE") "1%")
      )
      (libsource (lib "OLogic Nexus Vault") (part "=Resistance"))
    )
    (comp (ref "R23")
      (value "100")
      (footprint "RESC0603(1608)_N")
      (description "RES 100 OHM 1% 1/10W 0603 2017")
      (fields
        (field (name "PACKAGE (IMPERIAL)") "0603")
        (field (name "POWER") "100mW")
        (field (name "TOLERANCE") "1%")
        (field (name "RESISTANCE") "5.1K")
      )
      (libsource (lib "OLogic Nexus Vault") (part "=Resistance"))
    )
    (comp (ref "R24")
      (value "100")
      (footprint "RESC0603(1608)_N")
      (description "RES 100 OHM 1% 1/10W 0603 2017")
      (fields
        (field (name "PACKAGE (IMPERIAL)") "0603")
        (field (name "POWER") "100mW")
        (field (name "TOLERANCE") "1%")
        (field (name "RESISTANCE") "100")
      )
      (libsource (lib "OLogic Nexus Vault") (part "=Resistance"))
    )
    (comp (ref "R25")
      (value "1.0K")
      (footprint "RESC0603(1608)_N")
      (description "RES 1K OHM 1% 1/10W 0603")
      (fields
        (field (name "PACKAGE (IMPERIAL)") "0603")
        (field (name "POWER") "100mW")
        (field (name "RESISTANCE") "1k")
        (field (name "TOLERANCE") "1%")
      )
      (libsource (lib "OLogic Nexus Vault") (part "=Resistance"))
    )
    (comp (ref "R26")
      (value "10K")
      (footprint "RESC0603(1608)_M")
      (description "RES 10K OHM 1/10W 1% 0603 SMD")
      (fields
        (field (name "PACKAGE (IMPERIAL)") "0603")
        (field (name "RESISTANCE") "10")
        (field (name "POWER") "100mW")
        (field (name "TOLERANCE") "1%")
      )
      (libsource (lib "OLogic Nexus Vault") (part "=Resistance"))
    )
    (comp (ref "R27")
      (value "10K")
      (footprint "RESC0603(1608)_L")
      (description "RES 10K OHM 1/10W 1% 0603 SMD")
      (fields
        (field (name "PACKAGE (IMPERIAL)") "0603")
        (field (name "RESISTANCE") "10k")
        (field (name "POWER") "100mW")
        (field (name "TOLERANCE") "1%")
      )
      (libsource (lib "OLogic Nexus Vault") (part "=Resistance"))
    )
    (comp (ref "R28")
      (value "10K")
      (footprint "RESC0603(1608)_N")
      (description "RES 10K OHM 1/10W 1% 0603 SMD")
      (fields
        (field (name "PACKAGE (IMPERIAL)") "0603")
        (field (name "RESISTANCE") "10k")
        (field (name "POWER") "100mW")
        (field (name "TOLERANCE") "1%")
      )
      (libsource (lib "OLogic Nexus Vault") (part "=Resistance"))
    )
    (comp (ref "R29")
      (value "10K")
      (footprint "RESC0603(1608)_N")
      (description "RES 10K OHM 1/10W 1% 0603 SMD")
      (fields
        (field (name "PACKAGE (IMPERIAL)") "0603")
        (field (name "RESISTANCE") "10k")
        (field (name "POWER") "100mW")
        (field (name "TOLERANCE") "1%")
      )
      (libsource (lib "OLogic Nexus Vault") (part "=Resistance"))
    )
    (comp (ref "R30")
      (value "1.0K")
      (footprint "RESC0603(1608)_N")
      (description "RES 1K OHM 1% 1/10W 0603")
      (fields
        (field (name "PACKAGE (IMPERIAL)") "0603")
        (field (name "POWER") "100mW")
        (field (name "RESISTANCE") "10k")
        (field (name "TOLERANCE") "1%")
      )
      (libsource (lib "OLogic Nexus Vault") (part "=Resistance"))
    )
    (comp (ref "R31")
      (value "1.0K")
      (footprint "RESC0603(1608)_N")
      (description "RES 1K OHM 1% 1/10W 0603")
      (fields
        (field (name "PACKAGE (IMPERIAL)") "0603")
        (field (name "POWER") "100mW")
        (field (name "RESISTANCE") "1K")
        (field (name "TOLERANCE") "1%")
      )
      (libsource (lib "OLogic Nexus Vault") (part "=Resistance"))
    )
    (comp (ref "R32")
      (value "1.0K")
      (footprint "RESC0603(1608)_N")
      (description "RES 1K OHM 1% 1/10W 0603")
      (fields
        (field (name "PACKAGE (IMPERIAL)") "0603")
        (field (name "POWER") "100mW")
        (field (name "RESISTANCE") "1k")
        (field (name "TOLERANCE") "1%")
      )
      (libsource (lib "OLogic Nexus Vault") (part "=Resistance"))
    )
    (comp (ref "REG_IN")
      (value "TestPoint_BLK")
      (footprint "TestPoint-TH 42 mil")
      (description "Test Point - Black")
      (fields
        (field (name "MANUFACTURER PART NUMBER") "5001")
        (field (name "MANUFACTURER") "Keystone Electronics")
      )
      (libsource (lib "OLogic Nexus Vault") (part "TestPoint_BLK"))
    )
    (comp (ref "Spare_1")
      (value "TestPoint_BLK")
      (footprint "TestPoint-TH 42 mil")
      (description "Test Point - Black")
      (fields
        (field (name "MANUFACTURER PART NUMBER") "5001")
        (field (name "MANUFACTURER") "Keystone Electronics")
      )
      (libsource (lib "OLogic Nexus Vault") (part "TestPoint_BLK"))
    )
    (comp (ref "TP1")
      (value "TestPoint_BLK")
      (footprint "TestPoint-TH 42 mil")
      (description "Test Point - Black")
      (fields
        (field (name "MANUFACTURER PART NUMBER") "5001")
        (field (name "MANUFACTURER") "Keystone Electronics")
      )
      (libsource (lib "OLogic Nexus Vault") (part "TestPoint_BLK"))
    )
    (comp (ref "TP6")
      (value "TestPoint_BLK")
      (footprint "TestPoint-TH 42 mil")
      (description "Test Point - Black")
      (fields
        (field (name "MANUFACTURER PART NUMBER") "5001")
        (field (name "MANUFACTURER") "Keystone Electronics")
      )
      (libsource (lib "OLogic Nexus Vault") (part "TestPoint_BLK"))
    )
    (comp (ref "U1")
      (value "TPS7A4515KTTR")
      (footprint "TPS7A4515KTTR")
      (description "TPS7A4515KTTR, linear regulator")
      (libsource (lib "hdmi_lvds") (part "TPS7A4515KTTR"))
    )
    (comp (ref "U2")
      (value "INA180A1")
      (footprint "SOT-23-5_MC")
      (libsource (lib "hdmi_lvds") (part "INA180A1"))
    )
    (comp (ref "U3")
      (value "INA219")
      (footprint "INA219")
      (description "Current Monitor IC")
      (libsource (lib "hdmi_lvds") (part "INA219"))
    )
    (comp (ref "U4")
      (value "OPA2320")
      (footprint "SOIC-8_NoPad")
      (description "Dual Single Supply Rail-to-Rail OpAmp")
      (fields
        (field (name "MANUFACTURER PART NUMBER") "OPA2320AIDR")
        (field (name "BASE PART NUMBER") "OPA2320")
        (field (name "MANUFACTURER") "Texas Instruments")
      )
      (libsource (lib "OLogic Nexus Vault") (part "OPA2320"))
    )
    (comp (ref "U5")
      (value "LM334")
      (footprint "LM334")
      (description "LM334, Current source")
      (libsource (lib "hdmi_lvds") (part "LM334"))
    )
    (comp (ref "U6") (value "mcp9808") (footprint "8MSOP") (libsource (lib "hdmi_lvds") (part "mcp9808")))
    (comp (ref "U7")
      (value "mcp4728")
      (footprint "MCP4728")
      (description "MCP4728")
      (libsource (lib "hdmi_lvds") (part "mcp4728"))
    )
    (comp (ref "U8")
      (value "TCA9534APWR")
      (footprint "TCA9534APWR-Footprint-1")
      (description "IC I/O EXPANDER I2C 8B 16TSSOP")
      (libsource (lib "OLogic Nexus Vault") (part "TCA9534APWR"))
    )
    (comp (ref "U9")
      (value "OPA2320")
      (footprint "SOIC-8_NoPad")
      (description "Dual Single Supply Rail-to-Rail OpAmp")
      (fields
        (field (name "MANUFACTURER PART NUMBER") "OPA2320AIDR")
        (field (name "BASE PART NUMBER") "OPA2320")
        (field (name "MANUFACTURER") "Texas Instruments")
      )
      (libsource (lib "OLogic Nexus Vault") (part "OPA2320"))
    )
    (comp (ref "U10")
      (value "~")
      (footprint "TO-252_N")
      (libsource (lib "OLogic Nexus Vault") (part "PM-REG-LD29150-SOT3"))
    )
    (comp (ref "U11")
      (value "LD1117S33")
      (footprint "DSO-G3")
      (description "3.3 volt fixed regulator, 800mA")
      (libsource (lib "OLogic Nexus Vault") (part "LD1117S33"))
    )
    (comp (ref "U12") (value "LM2776") (footprint "SOt-23-6") (libsource (lib "*") (part "LM2776")))
    (comp (ref "U14")
      (value "TPS54331")
      (footprint "TPS54331")
      (libsource (lib "hdmi_lvds") (part "TPS54331"))
    )
    (comp (ref "VA_TP")
      (value "TestPoint_BLK")
      (footprint "TestPoint-TH 42 mil")
      (description "Test Point - Black")
      (fields
        (field (name "MANUFACTURER PART NUMBER") "5001")
        (field (name "MANUFACTURER") "Keystone Electronics")
      )
      (libsource (lib "OLogic Nexus Vault") (part "TestPoint_BLK"))
    )
  )
  (nets
    (net (code "1") (name "+5V0") (class "Default")
      (node (ref "+5V0") (pin "1") (pinfunction "1_1") (pintype "passive"))
      (node (ref "C21") (pin "1") (pinfunction "1_1") (pintype "passive"))
      (node (ref "C22") (pin "1") (pinfunction "1_1") (pintype "passive"))
      (node (ref "C25") (pin "1") (pinfunction "1_1") (pintype "passive"))
      (node (ref "C27") (pin "1") (pinfunction "1_1") (pintype "passive"))
      (node (ref "U10") (pin "3") (pinfunction "OUT_3") (pintype "power_in"))
      (node (ref "U11") (pin "3") (pinfunction "VIN_3") (pintype "power_in"))
      (node (ref "U12") (pin "3") (pinfunction "VIN_3") (pintype "passive"))
      (node (ref "U12") (pin "4") (pinfunction "EN_4") (pintype "passive"))
    )
    (net (code "2") (name "+VIN_SW") (class "Default")
      (node (ref "+VIN_SW") (pin "1") (pinfunction "1_1") (pintype "passive"))
      (node (ref "C18") (pin "1") (pinfunction "1_1") (pintype "passive"))
      (node (ref "C24") (pin "1") (pinfunction "1_1") (pintype "passive"))
      (node (ref "C33") (pin "1") (pinfunction "1_1") (pintype "passive"))
      (node (ref "C34") (pin "1") (pinfunction "1_1") (pintype "passive"))
      (node (ref "C35") (pin "1") (pinfunction "1_1") (pintype "passive"))
      (node (ref "C4") (pin "1") (pinfunction "1_1") (pintype "passive"))
      (node (ref "CN2") (pin "13") (pinfunction "13_13") (pintype "passive"))
      (node (ref "CN2") (pin "14") (pinfunction "14_14") (pintype "passive"))
      (node (ref "CN2") (pin "5") (pinfunction "5_5") (pintype "passive"))
      (node (ref "CN2") (pin "6") (pinfunction "6_6") (pintype "passive"))
      (node (ref "CN3") (pin "1") (pinfunction "1_1") (pintype "passive"))
      (node (ref "R29") (pin "1") (pinfunction "1_1") (pintype "passive"))
      (node (ref "R5") (pin "1") (pinfunction "1_1") (pintype "passive"))
      (node (ref "U10") (pin "1") (pinfunction "IN_1") (pintype "power_in"))
      (node (ref "U14") (pin "2") (pinfunction "VIN_2") (pintype "passive"))
      (node (ref "U4") (pin "8") (pinfunction "V+_8") (pintype "power_in"))
      (node (ref "U9") (pin "8") (pinfunction "V+_8") (pintype "power_in"))
    )
    (net (code "3") (name "-5V0") (class "Default")
      (node (ref "-5V0") (pin "1") (pinfunction "1_1") (pintype "passive"))
      (node (ref "C19") (pin "2") (pinfunction "2_2") (pintype "passive"))
      (node (ref "C26") (pin "1") (pinfunction "1_1") (pintype "passive"))
      (node (ref "C29") (pin "2") (pinfunction "2_2") (pintype "passive"))
      (node (ref "C5") (pin "1") (pinfunction "1_1") (pintype "passive"))
      (node (ref "C50") (pin "1") (pinfunction "1_1") (pintype "passive"))
      (node (ref "Q1") (pin "3") (pinfunction "C_3") (pintype "passive"))
      (node (ref "R24") (pin "2") (pinfunction "2_2") (pintype "passive"))
      (node (ref "R32") (pin "1") (pinfunction "1_1") (pintype "passive"))
      (node (ref "U12") (pin "1") (pinfunction "VOUT_1") (pintype "passive"))
      (node (ref "U4") (pin "4") (pinfunction "V-_4") (pintype "power_in"))
      (node (ref "U5") (pin "2") (pinfunction "-V_2") (pintype "passive"))
      (node (ref "U5") (pin "3") (pinfunction "-V_3") (pintype "passive"))
      (node (ref "U5") (pin "6") (pinfunction "-V_6") (pintype "passive"))
      (node (ref "U5") (pin "7") (pinfunction "-V_7") (pintype "passive"))
      (node (ref "U9") (pin "4") (pinfunction "V-_4") (pintype "power_in"))
    )
    (net (code "4") (name "/Current_Limit") (class "Default")
      (node (ref "CN2") (pin "3") (pinfunction "3_3") (pintype "passive"))
      (node (ref "LED2") (pin "2") (pinfunction "2_2") (pintype "passive"))
      (node (ref "Q2") (pin "3") (pinfunction "C_3") (pintype "passive"))
      (node (ref "U8") (pin "4") (pinfunction "P0_4") (pintype "bidirectional"))
    )
    (net (code "5") (name "/Debug_LED") (class "Default")
      (node (ref "LED3") (pin "2") (pinfunction "Cathode_2") (pintype "passive"))
      (node (ref "U8") (pin "6") (pinfunction "P2_6") (pintype "bidirectional"))
    )
    (net (code "6") (name "/I2C_SCL") (class "Default")
      (node (ref "CN2") (pin "1") (pinfunction "1_1") (pintype "passive"))
      (node (ref "I2C_SCL") (pin "1") (pinfunction "1_1") (pintype "passive"))
      (node (ref "R6") (pin "2") (pinfunction "2_2") (pintype "passive"))
      (node (ref "U3") (pin "4") (pinfunction "SCL_4") (pintype "passive"))
      (node (ref "U6") (pin "2") (pinfunction "SCL_2") (pintype "passive"))
      (node (ref "U7") (pin "2") (pinfunction "SCL_2") (pintype "passive"))
      (node (ref "U8") (pin "14") (pinfunction "SCL_14") (pintype "input"))
    )
    (net (code "7") (name "/I2C_SDA") (class "Default")
      (node (ref "CN2") (pin "2") (pinfunction "2_2") (pintype "passive"))
      (node (ref "I2C_SDA") (pin "1") (pinfunction "1_1") (pintype "passive"))
      (node (ref "R7") (pin "2") (pinfunction "2_2") (pintype "passive"))
      (node (ref "U3") (pin "3") (pinfunction "SDA_3") (pintype "passive"))
      (node (ref "U6") (pin "1") (pinfunction "SDA_1") (pintype "passive"))
      (node (ref "U7") (pin "3") (pinfunction "SDA_3") (pintype "passive"))
      (node (ref "U8") (pin "15") (pinfunction "SDA_15") (pintype "bidirectional"))
    )
    (net (code "8") (name "/IA_TP") (class "Default")
      (node (ref "IA_TP") (pin "1") (pinfunction "1_1") (pintype "passive"))
      (node (ref "R17") (pin "1") (pinfunction "1_1") (pintype "passive"))
      (node (ref "U7") (pin "7") (pinfunction "VoutB_7") (pintype "passive"))
    )
    (net (code "9") (name "/I_Sample") (class "Default")
      (node (ref "C6") (pin "1") (pinfunction "1_1") (pintype "passive"))
      (node (ref "CN2") (pin "11") (pinfunction "11_11") (pintype "passive"))
      (node (ref "I_sample") (pin "1") (pinfunction "1_1") (pintype "passive"))
      (node (ref "R11") (pin "2") (pinfunction "2_2") (pintype "passive"))
      (node (ref "U4") (pin "5") (pinfunction "INB+_5") (pintype "input"))
    )
    (net (code "10") (name "/OUTPUT_ENB") (class "Default")
      (node (ref "CN2") (pin "4") (pinfunction "4_4") (pintype "passive"))
      (node (ref "Q6") (pin "1") (pinfunction "G_1") (pintype "passive"))
      (node (ref "R20") (pin "1") (pinfunction "1_1") (pintype "passive"))
      (node (ref "U8") (pin "5") (pinfunction "P1_5") (pintype "bidirectional"))
    )
    (net (code "11") (name "/Pwr_Out") (class "Default")
      (node (ref "C3") (pin "1") (pinfunction "1_1") (pintype "passive"))
      (node (ref "C8") (pin "1") (pinfunction "1_1") (pintype "passive"))
      (node (ref "C9") (pin "1") (pinfunction "1_1") (pintype "passive"))
      (node (ref "CN1") (pin "1") (pinfunction "1_1") (pintype "passive"))
      (node (ref "CN1") (pin "2") (pinfunction "2_2") (pintype "passive"))
      (node (ref "CN1") (pin "6") (pinfunction "6_6") (pintype "passive"))
      (node (ref "CN1") (pin "7") (pinfunction "7_7") (pintype "passive"))
      (node (ref "D1") (pin "2") (pinfunction "K_2") (pintype "passive"))
      (node (ref "PWR_OUT") (pin "1") (pinfunction "1_1") (pintype "passive"))
      (node (ref "R1") (pin "1") (pinfunction "1_1") (pintype "passive"))
      (node (ref "R26") (pin "2") (pinfunction "2_2") (pintype "passive"))
      (node (ref "R3") (pin "2") (pinfunction "2_2") (pintype "passive"))
      (node (ref "U5") (pin "4") (pinfunction "+V_4") (pintype "passive"))
    )
    (net (code "12") (name "/Pwr_Out_Sample") (class "Default")
      (node (ref "C13") (pin "1") (pinfunction "1_1") (pintype "passive"))
      (node (ref "R10") (pin "2") (pinfunction "2_2") (pintype "passive"))
      (node (ref "R3") (pin "1") (pinfunction "1_1") (pintype "passive"))
      (node (ref "U1") (pin "4") (pinfunction "OUT_4") (pintype "passive"))
    )
    (net (code "13") (name "/VA_TP") (class "Default")
      (node (ref "U7") (pin "6") (pinfunction "VoutA_6") (pintype "passive"))
      (node (ref "U9") (pin "3") (pinfunction "INA+_3") (pintype "input"))
      (node (ref "VA_TP") (pin "1") (pinfunction "1_1") (pintype "passive"))
    )
    (net (code "14") (name "/VA_TP_GAIN") (class "Default")
      (node (ref "C1") (pin "2") (pinfunction "2_2") (pintype "passive"))
      (node (ref "R12") (pin "1") (pinfunction "1_1") (pintype "passive"))
      (node (ref "R4") (pin "2") (pinfunction "2_2") (pintype "passive"))
      (node (ref "U9") (pin "1") (pinfunction "OUTA_1") (pintype "output"))
    )
    (net (code "15") (name "/V_offset_adj") (class "Default")
      (node (ref "OSA_TP") (pin "1") (pinfunction "1_1") (pintype "passive"))
      (node (ref "R9") (pin "2") (pinfunction "2_2") (pintype "passive"))
      (node (ref "U7") (pin "8") (pinfunction "VoutC_8") (pintype "passive"))
    )
    (net (code "16") (name "/{slash}INT") (class "Default")
      (node (ref "CN2") (pin "10") (pinfunction "10_10") (pintype "passive"))
      (node (ref "R15") (pin "1") (pinfunction "1_1") (pintype "passive"))
      (node (ref "U8") (pin "13") (pinfunction "~{INT}_13") (pintype "output"))
    )
    (net (code "17") (name "/{slash}RST") (class "Default")
      (node (ref "CN2") (pin "9") (pinfunction "9_9") (pintype "passive"))
      (node (ref "TP1") (pin "1") (pinfunction "1_1") (pintype "passive"))
    )
    (net (code "18") (name "3V3") (class "Default")
      (node (ref "3V3") (pin "1") (pinfunction "1_1") (pintype "passive"))
      (node (ref "C14") (pin "1") (pinfunction "1_1") (pintype "passive"))
      (node (ref "C15") (pin "1") (pinfunction "1_1") (pintype "passive"))
      (node (ref "C16") (pin "1") (pinfunction "1_1") (pintype "passive"))
      (node (ref "C2") (pin "1") (pinfunction "1_1") (pintype "passive"))
      (node (ref "C23") (pin "1") (pinfunction "1_1") (pintype "passive"))
      (node (ref "C28") (pin "1") (pinfunction "1_1") (pintype "passive"))
      (node (ref "C7") (pin "1") (pinfunction "1_1") (pintype "passive"))
      (node (ref "R15") (pin "2") (pinfunction "2_2") (pintype "passive"))
      (node (ref "R19") (pin "1") (pinfunction "1_1") (pintype "passive"))
      (node (ref "R25") (pin "1") (pinfunction "1_1") (pintype "passive"))
      (node (ref "R28") (pin "1") (pinfunction "1_1") (pintype "passive"))
      (node (ref "R31") (pin "1") (pinfunction "1_1") (pintype "passive"))
      (node (ref "R6") (pin "1") (pinfunction "1_1") (pintype "passive"))
      (node (ref "R7") (pin "1") (pinfunction "1_1") (pintype "passive"))
      (node (ref "U11") (pin "2") (pinfunction "VOUT_2") (pintype "power_in"))
      (node (ref "U11") (pin "4") (pinfunction "TAB_4") (pintype "power_in"))
      (node (ref "U2") (pin "5") (pinfunction "VCC_5") (pintype "passive"))
      (node (ref "U3") (pin "5") (pinfunction "VDD_5") (pintype "passive"))
      (node (ref "U6") (pin "8") (pinfunction "VDD_8") (pintype "passive"))
      (node (ref "U7") (pin "1") (pinfunction "VDD_1") (pintype "passive"))
      (node (ref "U8") (pin "16") (pinfunction "VCC_16") (pintype "power_in"))
    )
    (net (code "19") (name "GND") (class "Default")
      (node (ref "C10") (pin "2") (pinfunction "2_2") (pintype "passive"))
      (node (ref "C11") (pin "2") (pinfunction "2_2") (pintype "passive"))
      (node (ref "C12") (pin "2") (pinfunction "2_2") (pintype "passive"))
      (node (ref "C13") (pin "2") (pinfunction "2_2") (pintype "passive"))
      (node (ref "C14") (pin "2") (pinfunction "2_2") (pintype "passive"))
      (node (ref "C15") (pin "2") (pinfunction "2_2") (pintype "passive"))
      (node (ref "C16") (pin "2") (pinfunction "2_2") (pintype "passive"))
      (node (ref "C18") (pin "2") (pinfunction "2_2") (pintype "passive"))
      (node (ref "C19") (pin "1") (pinfunction "1_1") (pintype "passive"))
      (node (ref "C2") (pin "2") (pinfunction "2_2") (pintype "passive"))
      (node (ref "C21") (pin "2") (pinfunction "2_2") (pintype "passive"))
      (node (ref "C22") (pin "2") (pinfunction "2_2") (pintype "passive"))
      (node (ref "C23") (pin "2") (pinfunction "2_2") (pintype "passive"))
      (node (ref "C24") (pin "2") (pinfunction "2_2") (pintype "passive"))
      (node (ref "C25") (pin "2") (pinfunction "2_2") (pintype "passive"))
      (node (ref "C26") (pin "2") (pinfunction "2_2") (pintype "passive"))
      (node (ref "C27") (pin "2") (pinfunction "2_2") (pintype "passive"))
      (node (ref "C28") (pin "2") (pinfunction "2_2") (pintype "passive"))
      (node (ref "C29") (pin "1") (pinfunction "1_1") (pintype "passive"))
      (node (ref "C3") (pin "2") (pinfunction "2_2") (pintype "passive"))
      (node (ref "C32") (pin "2") (pinfunction "2_2") (pintype "passive"))
      (node (ref "C33") (pin "2") (pinfunction "2_2") (pintype "passive"))
      (node (ref "C34") (pin "2") (pinfunction "2_2") (pintype "passive"))
      (node (ref "C35") (pin "2") (pinfunction "2_2") (pintype "passive"))
      (node (ref "C37") (pin "2") (pinfunction "2_2") (pintype "passive"))
      (node (ref "C38") (pin "2") (pinfunction "2_2") (pintype "passive"))
      (node (ref "C39") (pin "2") (pinfunction "2_2") (pintype "passive"))
      (node (ref "C4") (pin "2") (pinfunction "2_2") (pintype "passive"))
      (node (ref "C41") (pin "1") (pinfunction "1_1") (pintype "passive"))
      (node (ref "C42") (pin "2") (pinfunction "2_2") (pintype "passive"))
      (node (ref "C43") (pin "2") (pinfunction "2_2") (pintype "passive"))
      (node (ref "C44") (pin "2") (pinfunction "2_2") (pintype "passive"))
      (node (ref "C45") (pin "2") (pinfunction "2_2") (pintype "passive"))
      (node (ref "C46") (pin "2") (pinfunction "2_2") (pintype "passive"))
      (node (ref "C5") (pin "2") (pinfunction "2_2") (pintype "passive"))
      (node (ref "C50") (pin "2") (pinfunction "2_2") (pintype "passive"))
      (node (ref "C6") (pin "2") (pinfunction "2_2") (pintype "passive"))
      (node (ref "C7") (pin "2") (pinfunction "2_2") (pintype "passive"))
      (node (ref "C8") (pin "2") (pinfunction "2_2") (pintype "passive"))
      (node (ref "C9") (pin "2") (pinfunction "2_2") (pintype "passive"))
      (node (ref "CN1") (pin "10") (pinfunction "10_10") (pintype "passive"))
      (node (ref "CN1") (pin "4") (pinfunction "4_4") (pintype "passive"))
      (node (ref "CN1") (pin "5") (pinfunction "5_5") (pintype "passive"))
      (node (ref "CN1") (pin "9") (pinfunction "9_9") (pintype "passive"))
      (node (ref "CN2") (pin "15") (pinfunction "15_15") (pintype "passive"))
      (node (ref "CN2") (pin "16") (pinfunction "16_16") (pintype "passive"))
      (node (ref "CN2") (pin "7") (pinfunction "7_7") (pintype "passive"))
      (node (ref "CN2") (pin "8") (pinfunction "8_8") (pintype "passive"))
      (node (ref "CN4") (pin "2") (pinfunction "2_2") (pintype "passive"))
      (node (ref "CN5") (pin "2") (pinfunction "2_2") (pintype "passive"))
      (node (ref "D1") (pin "1") (pinfunction "A_1") (pintype "passive"))
      (node (ref "D3") (pin "1") (pinfunction "A_1") (pintype "passive"))
      (node (ref "GND") (pin "1") (pinfunction "1_1") (pintype "passive"))
      (node (ref "GND3") (pin "1") (pinfunction "1_1") (pintype "passive"))
      (node (ref "GND4") (pin "1") (pinfunction "1_1") (pintype "passive"))
      (node (ref "GND5") (pin "1") (pinfunction "1_1") (pintype "passive"))
      (node (ref "LED1") (pin "2") (pinfunction "Cathode_2") (pintype "passive"))
      (node (ref "Q2") (pin "2") (pinfunction "E_2") (pintype "passive"))
      (node (ref "Q4") (pin "2") (pinfunction "S_2") (pintype "passive"))
      (node (ref "Q6") (pin "2") (pinfunction "S_2") (pintype "passive"))
      (node (ref "R13") (pin "1") (pinfunction "1_1") (pintype "passive"))
      (node (ref "R18") (pin "2") (pinfunction "2_2") (pintype "passive"))
      (node (ref "R20") (pin "2") (pinfunction "2_2") (pintype "passive"))
      (node (ref "R22") (pin "2") (pinfunction "2_2") (pintype "passive"))
      (node (ref "R27") (pin "2") (pinfunction "2_2") (pintype "passive"))
      (node (ref "R32") (pin "2") (pinfunction "2_2") (pintype "passive"))
      (node (ref "U10") (pin "4") (pinfunction "TAB_4") (pintype "passive"))
      (node (ref "U11") (pin "1") (pinfunction "GND_1") (pintype "power_in"))
      (node (ref "U12") (pin "2") (pinfunction "GND_2") (pintype "passive"))
      (node (ref "U14") (pin "7") (pinfunction "GND_7") (pintype "passive"))
      (node (ref "U14") (pin "9") (pinfunction "PPAD_9") (pintype "passive"))
      (node (ref "U2") (pin "2") (pinfunction "GND_2") (pintype "passive"))
      (node (ref "U3") (pin "1") (pinfunction "A1_1") (pintype "passive"))
      (node (ref "U3") (pin "2") (pinfunction "A0_2") (pintype "passive"))
      (node (ref "U3") (pin "6") (pinfunction "GND_6") (pintype "passive"))
      (node (ref "U6") (pin "4") (pinfunction "GND_4") (pintype "passive"))
      (node (ref "U6") (pin "5") (pinfunction "A2_5") (pintype "passive"))
      (node (ref "U6") (pin "6") (pinfunction "A1_6") (pintype "passive"))
      (node (ref "U6") (pin "7") (pinfunction "A1_7") (pintype "passive"))
      (node (ref "U7") (pin "10") (pinfunction "VSS_10") (pintype "passive"))
      (node (ref "U7") (pin "4") (pinfunction "/LDAC_4") (pintype "passive"))
      (node (ref "U8") (pin "1") (pinfunction "A0_1") (pintype "input"))
      (node (ref "U8") (pin "2") (pinfunction "A1_2") (pintype "input"))
      (node (ref "U8") (pin "3") (pinfunction "A2_3") (pintype "input"))
      (node (ref "U8") (pin "8") (pinfunction "GND_8") (pintype "power_in"))
      (node (ref "U9") (pin "5") (pinfunction "INB+_5") (pintype "input"))
    )
    (net (code "20") (name "Net-(C32-Pad1)") (class "Default")
      (node (ref "C32") (pin "1") (pinfunction "1_1") (pintype "passive"))
      (node (ref "C37") (pin "1") (pinfunction "1_1") (pintype "passive"))
      (node (ref "C38") (pin "1") (pinfunction "1_1") (pintype "passive"))
      (node (ref "CN3") (pin "2") (pinfunction "2_2") (pintype "passive"))
      (node (ref "FB1") (pin "1") (pinfunction "1_1") (pintype "passive"))
      (node (ref "L1") (pin "2") (pinfunction "2_2") (pintype "passive"))
      (node (ref "R2") (pin "1") (pinfunction "1_1") (pintype "passive"))
    )
    (net (code "21") (name "Net-(C40-Pad2)") (class "Default")
      (node (ref "C40") (pin "2") (pinfunction "2_2") (pintype "passive"))
      (node (ref "R18") (pin "1") (pinfunction "1_1") (pintype "passive"))
    )
    (net (code "22") (name "Net-(C42-Pad1)") (class "Default")
      (node (ref "C42") (pin "1") (pinfunction "1_1") (pintype "passive"))
      (node (ref "FB1") (pin "2") (pinfunction "2_2") (pintype "passive"))
      (node (ref "L2") (pin "1") (pinfunction "1_1") (pintype "passive"))
    )
    (net (code "23") (name "Net-(D2-A)") (class "Default")
      (node (ref "D2") (pin "1") (pinfunction "A_1") (pintype "passive"))
      (node (ref "Q5") (pin "1") (pinfunction "B_1") (pintype "passive"))
      (node (ref "R14") (pin "1") (pinfunction "1_1") (pintype "passive"))
    )
    (net (code "24") (name "Net-(D2-C)") (class "Default")
      (node (ref "D2") (pin "2") (pinfunction "C_2") (pintype "passive"))
      (node (ref "Q5") (pin "2") (pinfunction "E_2") (pintype "passive"))
      (node (ref "R2") (pin "2") (pinfunction "2_2") (pintype "passive"))
    )
    (net (code "25") (name "Net-(D3-K)") (class "Default")
      (node (ref "C36") (pin "2") (pinfunction "2_2") (pintype "passive"))
      (node (ref "D3") (pin "2") (pinfunction "K_2") (pintype "passive"))
      (node (ref "L1") (pin "1") (pinfunction "1_1") (pintype "passive"))
      (node (ref "U14") (pin "8") (pinfunction "PH_8") (pintype "passive"))
    )
    (net (code "26") (name "Net-(LED1-Anode)") (class "Default")
      (node (ref "LED1") (pin "1") (pinfunction "Anode_1") (pintype "passive"))
      (node (ref "R25") (pin "2") (pinfunction "2_2") (pintype "passive"))
    )
    (net (code "27") (name "Net-(LED2-Pad1)") (class "Default")
      (node (ref "LED2") (pin "1") (pinfunction "1_1") (pintype "passive"))
      (node (ref "R19") (pin "2") (pinfunction "2_2") (pintype "passive"))
    )
    (net (code "28") (name "Net-(LED3-Anode)") (class "Default")
      (node (ref "LED3") (pin "1") (pinfunction "Anode_1") (pintype "passive"))
      (node (ref "R31") (pin "2") (pinfunction "2_2") (pintype "passive"))
    )
    (net (code "29") (name "Net-(Q1-B)") (class "Default")
      (node (ref "Q1") (pin "1") (pinfunction "B_1") (pintype "passive"))
      (node (ref "U4") (pin "1") (pinfunction "OUTA_1") (pintype "output"))
    )
    (net (code "30") (name "Net-(Q1-E)") (class "Default")
      (node (ref "C47") (pin "1") (pinfunction "1_1") (pintype "passive"))
      (node (ref "Q1") (pin "2") (pinfunction "E_2") (pintype "passive"))
      (node (ref "R14") (pin "2") (pinfunction "2_2") (pintype "passive"))
      (node (ref "R5") (pin "2") (pinfunction "2_2") (pintype "passive"))
      (node (ref "R8") (pin "1") (pinfunction "1_1") (pintype "passive"))
      (node (ref "TP6") (pin "1") (pinfunction "1_1") (pintype "passive"))
      (node (ref "U1") (pin "3") (pinfunction "GND_3") (pintype "passive"))
      (node (ref "U1") (pin "6") (pinfunction "TAB_6") (pintype "passive"))
    )
    (net (code "31") (name "Net-(Q2-B)") (class "Default")
      (node (ref "Q2") (pin "1") (pinfunction "B_1") (pintype "passive"))
      (node (ref "R30") (pin "1") (pinfunction "1_1") (pintype "passive"))
    )
    (net (code "32") (name "Net-(Q3-B)") (class "Default")
      (node (ref "CN5") (pin "1") (pinfunction "1_1") (pintype "passive"))
      (node (ref "Q3") (pin "1") (pinfunction "B_1") (pintype "passive"))
      (node (ref "R16") (pin "2") (pinfunction "2_2") (pintype "passive"))
    )
    (net (code "33") (name "Net-(Q3-C)") (class "Default")
      (node (ref "Q3") (pin "3") (pinfunction "C_3") (pintype "passive"))
      (node (ref "Q4") (pin "3") (pinfunction "D_3") (pintype "passive"))
      (node (ref "R12") (pin "2") (pinfunction "2_2") (pintype "passive"))
      (node (ref "U4") (pin "3") (pinfunction "INA+_3") (pintype "input"))
    )
    (net (code "34") (name "Net-(Q3-E)") (class "Default")
      (node (ref "Q3") (pin "2") (pinfunction "E_2") (pintype "passive"))
      (node (ref "R22") (pin "1") (pinfunction "1_1") (pintype "passive"))
    )
    (net (code "35") (name "Net-(Q4-G)") (class "Default")
      (node (ref "Q4") (pin "1") (pinfunction "G_1") (pintype "passive"))
      (node (ref "Q6") (pin "3") (pinfunction "D_3") (pintype "passive"))
      (node (ref "R28") (pin "2") (pinfunction "2_2") (pintype "passive"))
    )
    (net (code "36") (name "Net-(Q5-C)") (class "Default")
      (node (ref "Q5") (pin "3") (pinfunction "C_3") (pintype "passive"))
      (node (ref "R27") (pin "1") (pinfunction "1_1") (pintype "passive"))
      (node (ref "U14") (pin "5") (pinfunction "VSENSE_5") (pintype "passive"))
    )
    (net (code "37") (name "Net-(U1-SENSE)") (class "Default")
      (node (ref "CN1") (pin "3") (pinfunction "3_3") (pintype "passive"))
      (node (ref "CN1") (pin "8") (pinfunction "8_8") (pintype "passive"))
      (node (ref "R1") (pin "2") (pinfunction "2_2") (pintype "passive"))
      (node (ref "U1") (pin "5") (pinfunction "SENSE_5") (pintype "passive"))
    )
    (net (code "38") (name "Net-(U2-IN+)") (class "Default")
      (node (ref "C31") (pin "1") (pinfunction "1_1") (pintype "passive"))
      (node (ref "R10") (pin "1") (pinfunction "1_1") (pintype "passive"))
      (node (ref "U2") (pin "3") (pinfunction "IN+_3") (pintype "passive"))
      (node (ref "U3") (pin "8") (pinfunction "Vin+_8") (pintype "passive"))
    )
    (net (code "39") (name "Net-(U2-IN-)") (class "Default")
      (node (ref "C31") (pin "2") (pinfunction "2_2") (pintype "passive"))
      (node (ref "R26") (pin "1") (pinfunction "1_1") (pintype "passive"))
      (node (ref "U2") (pin "4") (pinfunction "IN-_4") (pintype "passive"))
      (node (ref "U3") (pin "7") (pinfunction "Vin-_7") (pintype "passive"))
    )
    (net (code "40") (name "Net-(U2-OUT)") (class "Default")
      (node (ref "R11") (pin "1") (pinfunction "1_1") (pintype "passive"))
      (node (ref "U2") (pin "1") (pinfunction "OUT_1") (pintype "passive"))
    )
    (net (code "41") (name "Net-(U4A-INA-)") (class "Default")
      (node (ref "C47") (pin "2") (pinfunction "2_2") (pintype "passive"))
      (node (ref "R8") (pin "2") (pinfunction "2_2") (pintype "passive"))
      (node (ref "R9") (pin "1") (pinfunction "1_1") (pintype "passive"))
      (node (ref "U4") (pin "2") (pinfunction "INA-_2") (pintype "input"))
    )
    (net (code "42") (name "Net-(U4B-INB-)") (class "Default")
      (node (ref "C30") (pin "2") (pinfunction "2_2") (pintype "passive"))
      (node (ref "R17") (pin "2") (pinfunction "2_2") (pintype "passive"))
      (node (ref "R21") (pin "1") (pinfunction "1_1") (pintype "passive"))
      (node (ref "U4") (pin "6") (pinfunction "INB-_6") (pintype "input"))
    )
    (net (code "43") (name "Net-(U4B-OUTB)") (class "Default")
      (node (ref "C30") (pin "1") (pinfunction "1_1") (pintype "passive"))
      (node (ref "R16") (pin "1") (pinfunction "1_1") (pintype "passive"))
      (node (ref "R21") (pin "2") (pinfunction "2_2") (pintype "passive"))
      (node (ref "R30") (pin "2") (pinfunction "2_2") (pintype "passive"))
      (node (ref "U4") (pin "7") (pinfunction "OUTB_7") (pintype "output"))
    )
    (net (code "44") (name "Net-(U5-R)") (class "Default")
      (node (ref "R24") (pin "1") (pinfunction "1_1") (pintype "passive"))
      (node (ref "U5") (pin "1") (pinfunction "R_1") (pintype "passive"))
    )
    (net (code "45") (name "Net-(U7-VoutD)") (class "Default")
      (node (ref "Spare_1") (pin "1") (pinfunction "1_1") (pintype "passive"))
      (node (ref "U7") (pin "9") (pinfunction "VoutD_9") (pintype "passive"))
    )
    (net (code "46") (name "Net-(U9A-INA-)") (class "Default")
      (node (ref "C1") (pin "1") (pinfunction "1_1") (pintype "passive"))
      (node (ref "R13") (pin "2") (pinfunction "2_2") (pintype "passive"))
      (node (ref "R4") (pin "1") (pinfunction "1_1") (pintype "passive"))
      (node (ref "U9") (pin "2") (pinfunction "INA-_2") (pintype "input"))
    )
    (net (code "47") (name "Net-(U9B-INB-)") (class "Default")
      (node (ref "R23") (pin "1") (pinfunction "1_1") (pintype "passive"))
      (node (ref "U9") (pin "6") (pinfunction "INB-_6") (pintype "input"))
    )
    (net (code "48") (name "Net-(U9B-OUTB)") (class "Default")
      (node (ref "R23") (pin "2") (pinfunction "2_2") (pintype "passive"))
      (node (ref "U9") (pin "7") (pinfunction "OUTB_7") (pintype "output"))
    )
    (net (code "49") (name "Net-(U12-C1+)") (class "Default")
      (node (ref "C17") (pin "1") (pinfunction "1_1") (pintype "passive"))
      (node (ref "U12") (pin "5") (pinfunction "C1+_5") (pintype "passive"))
    )
    (net (code "50") (name "Net-(U12-C1-)") (class "Default")
      (node (ref "C17") (pin "2") (pinfunction "2_2") (pintype "passive"))
      (node (ref "U12") (pin "6") (pinfunction "C1-_6") (pintype "passive"))
    )
    (net (code "51") (name "Net-(U14-BOOT)") (class "Default")
      (node (ref "C36") (pin "1") (pinfunction "1_1") (pintype "passive"))
      (node (ref "U14") (pin "1") (pinfunction "BOOT_1") (pintype "passive"))
    )
    (net (code "52") (name "Net-(U14-COMP)") (class "Default")
      (node (ref "C40") (pin "1") (pinfunction "1_1") (pintype "passive"))
      (node (ref "C41") (pin "2") (pinfunction "2_2") (pintype "passive"))
      (node (ref "U14") (pin "6") (pinfunction "COMP_6") (pintype "passive"))
    )
    (net (code "53") (name "Net-(U14-EN)") (class "Default")
      (node (ref "CN4") (pin "1") (pinfunction "1_1") (pintype "passive"))
      (node (ref "R29") (pin "2") (pinfunction "2_2") (pintype "passive"))
      (node (ref "U14") (pin "3") (pinfunction "EN_3") (pintype "passive"))
    )
    (net (code "54") (name "Net-(U14-SS)") (class "Default")
      (node (ref "C39") (pin "1") (pinfunction "1_1") (pintype "passive"))
      (node (ref "U14") (pin "4") (pinfunction "SS_4") (pintype "passive"))
    )
    (net (code "55") (name "REG_VIN") (class "Default")
      (node (ref "C10") (pin "1") (pinfunction "1_1") (pintype "passive"))
      (node (ref "C11") (pin "1") (pinfunction "1_1") (pintype "passive"))
      (node (ref "C12") (pin "1") (pinfunction "1_1") (pintype "passive"))
      (node (ref "C43") (pin "1") (pinfunction "1_1") (pintype "passive"))
      (node (ref "C44") (pin "1") (pinfunction "1_1") (pintype "passive"))
      (node (ref "C45") (pin "1") (pinfunction "1_1") (pintype "passive"))
      (node (ref "C46") (pin "1") (pinfunction "1_1") (pintype "passive"))
      (node (ref "L2") (pin "2") (pinfunction "2_2") (pintype "passive"))
      (node (ref "REG_IN") (pin "1") (pinfunction "1_1") (pintype "passive"))
      (node (ref "U1") (pin "1") (pinfunction "/SHDN_1") (pintype "passive"))
      (node (ref "U1") (pin "2") (pinfunction "IN_2") (pintype "passive"))
    )
    (net (code "56") (name "unconnected-(CN2-Pad12)") (class "Default")
      (node (ref "CN2") (pin "12") (pinfunction "12_12") (pintype "passive+no_connect"))
    )
    (net (code "57") (name "unconnected-(U5-NC-Pad5)") (class "Default")
      (node (ref "U5") (pin "5") (pinfunction "NC_5") (pintype "passive+no_connect"))
    )
    (net (code "58") (name "unconnected-(U5-NC-Pad8)") (class "Default")
      (node (ref "U5") (pin "8") (pinfunction "NC_8") (pintype "passive+no_connect"))
    )
    (net (code "59") (name "unconnected-(U6-Alert-Pad3)") (class "Default")
      (node (ref "U6") (pin "3") (pinfunction "Alert_3") (pintype "passive+no_connect"))
    )
    (net (code "60") (name "unconnected-(U7-RDY-Pad5)") (class "Default")
      (node (ref "U7") (pin "5") (pinfunction "RDY_5") (pintype "passive+no_connect"))
    )
    (net (code "61") (name "unconnected-(U8-P3-Pad7)") (class "Default")
      (node (ref "U8") (pin "7") (pinfunction "P3_7") (pintype "bidirectional+no_connect"))
    )
    (net (code "62") (name "unconnected-(U8-P4-Pad9)") (class "Default")
      (node (ref "U8") (pin "9") (pinfunction "P4_9") (pintype "bidirectional+no_connect"))
    )
    (net (code "63") (name "unconnected-(U8-P5-Pad10)") (class "Default")
      (node (ref "U8") (pin "10") (pinfunction "P5_10") (pintype "bidirectional+no_connect"))
    )
    (net (code "64") (name "unconnected-(U8-P6-Pad11)") (class "Default")
      (node (ref "U8") (pin "11") (pinfunction "P6_11") (pintype "bidirectional+no_connect"))
    )
    (net (code "65") (name "unconnected-(U8-P7-Pad12)") (class "Default")
      (node (ref "U8") (pin "12") (pinfunction "P7_12") (pintype "bidirectional+no_connect"))
    )
  )
)
